# PX4FMUv2_4_6_10.net
KiCad netlist of a schematic drawn in Altium Designer
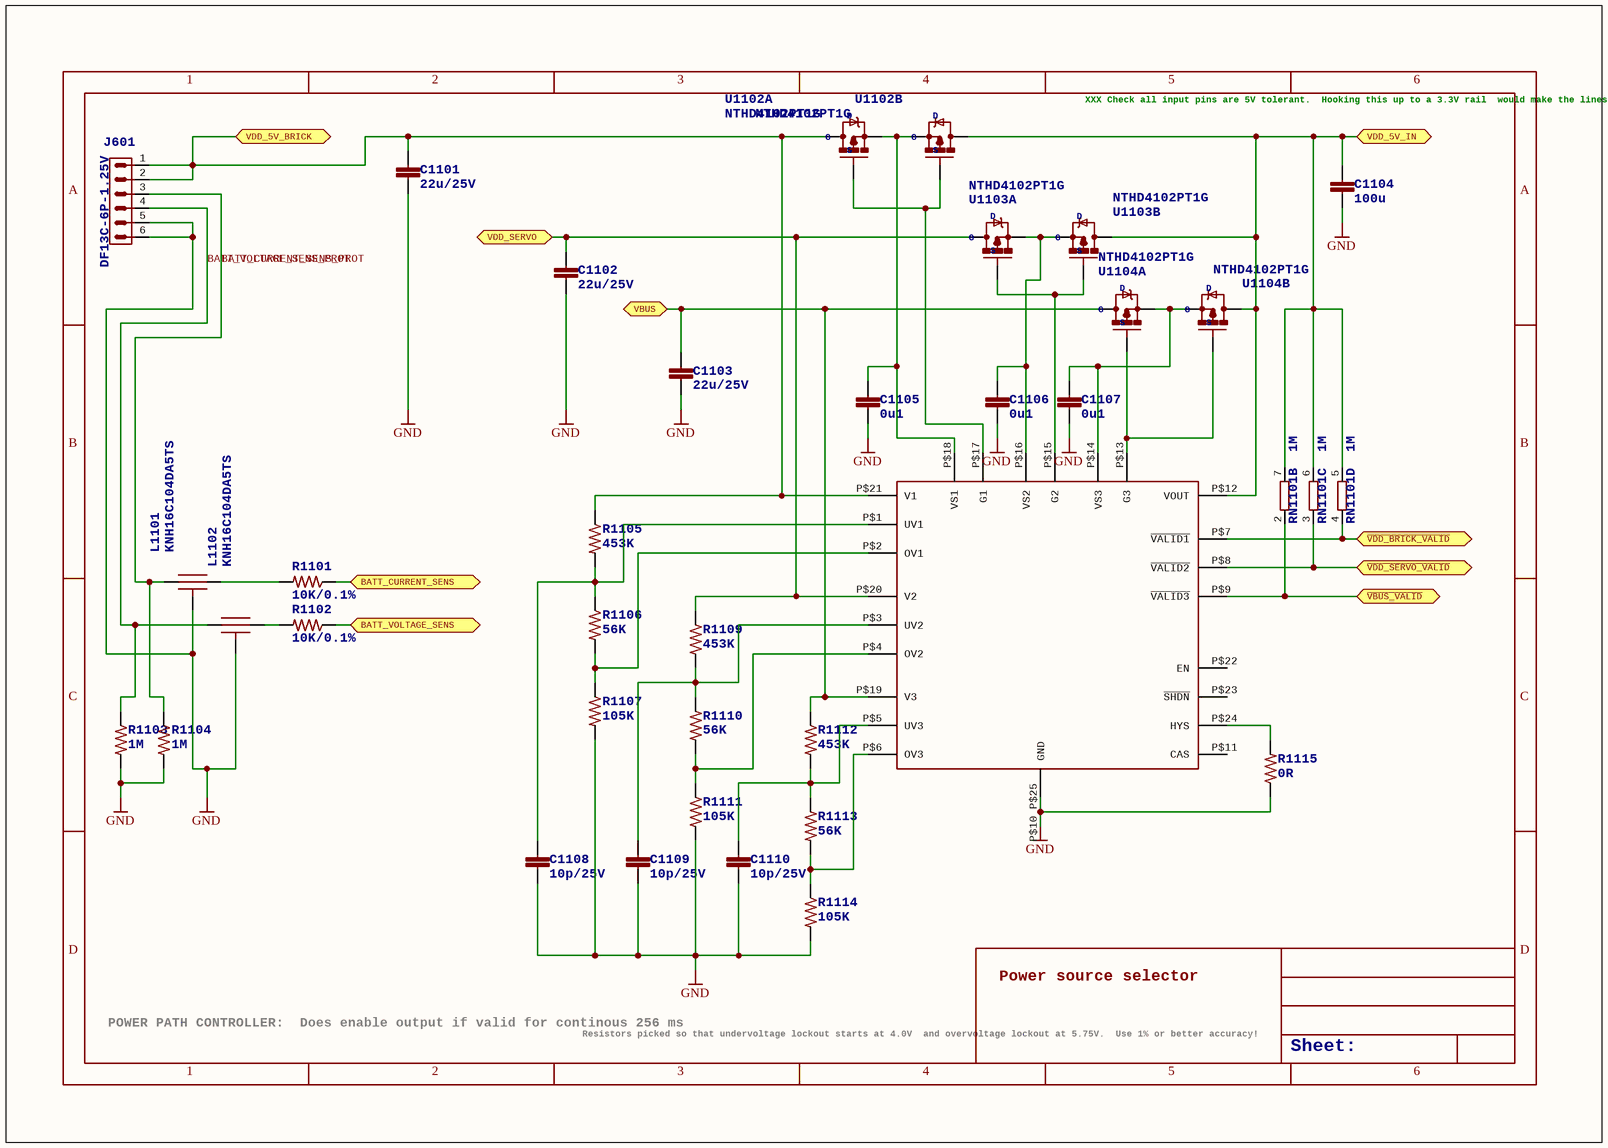
[diagram p0: PX4FMUv2.4.6_10.SchDoc]

(export (version "E")
  (design (tool "Eeschema 10.0.6"))
  (components
    (comp (ref "C1101")
      (value "22u/25V")
      (footprint "0805-CAP")
      (description "CapacitorStandard 0603 ceramic capacitor, and 0.1\" leaded capacitor.")
      (fields (field (name "PARTNO") "CL21A226MAQNNNE"))
      (libsource (lib "pixhawk2") (part "CAP0805"))
    )
    (comp (ref "C1102")
      (value "22u/25V")
      (footprint "0805-CAP")
      (description "CapacitorStandard 0603 ceramic capacitor, and 0.1\" leaded capacitor.")
      (fields (field (name "PARTNO") "CL21A226MAQNNNE"))
      (libsource (lib "pixhawk2") (part "CAP0805"))
    )
    (comp (ref "C1103")
      (value "22u/25V")
      (footprint "0805-CAP")
      (description "CapacitorStandard 0603 ceramic capacitor, and 0.1\" leaded capacitor.")
      (fields (field (name "PARTNO") "CL21A226MAQNNNE"))
      (libsource (lib "pixhawk2") (part "CAP0805"))
    )
    (comp (ref "C1104")
      (value "100u")
      (footprint "1206-CAP")
      (description "CapacitorStandard 0603 ceramic capacitor, and 0.1\" leaded capacitor.")
      (fields (field (name "PARTNO") "C3216X5R1A107M160AC"))
      (libsource (lib "pixhawk2") (part "CAP1206"))
    )
    (comp (ref "C1105")
      (value "0u1")
      (footprint "0402-CAP")
      (description "CapacitorStandard 0603 ceramic capacitor, and 0.1\" leaded capacitor.")
      (fields (field (name "PARTNO") "C1005X7R1E104K050BB"))
      (libsource (lib "pixhawk2") (part "CAP0402"))
    )
    (comp (ref "C1106")
      (value "0u1")
      (footprint "0402-CAP")
      (description "CapacitorStandard 0603 ceramic capacitor, and 0.1\" leaded capacitor.")
      (fields (field (name "PARTNO") "C1005X7R1E104K050BB"))
      (libsource (lib "pixhawk2") (part "CAP0402"))
    )
    (comp (ref "C1107")
      (value "0u1")
      (footprint "0402-CAP")
      (description "CapacitorStandard 0603 ceramic capacitor, and 0.1\" leaded capacitor.")
      (fields (field (name "PARTNO") "C1005X7R1E104K050BB"))
      (libsource (lib "pixhawk2") (part "CAP0402"))
    )
    (comp (ref "C1108")
      (value "10p/25V")
      (footprint "0402-CAP")
      (description "CapacitorStandard 0603 ceramic capacitor, and 0.1\" leaded capacitor.")
      (fields (field (name "PARTNO") "C0402C100J3GACTU"))
      (libsource (lib "pixhawk2") (part "CAP0402"))
    )
    (comp (ref "C1109")
      (value "10p/25V")
      (footprint "0402-CAP")
      (description "CapacitorStandard 0603 ceramic capacitor, and 0.1\" leaded capacitor.")
      (fields (field (name "PARTNO") "C0402C100J3GACTU"))
      (libsource (lib "pixhawk2") (part "CAP0402"))
    )
    (comp (ref "C1110")
      (value "10p/25V")
      (footprint "0402-CAP")
      (description "CapacitorStandard 0603 ceramic capacitor, and 0.1\" leaded capacitor.")
      (fields (field (name "PARTNO") "C0402C100J3GACTU"))
      (libsource (lib "pixhawk2") (part "CAP0402"))
    )
    (comp (ref "J601")
      (value "DF13C-6P-1.25V")
      (footprint "DF13C-6P-1.25V")
      (description "DF13-6P 1.25mm Pitch Miniature Crimping Connector.")
      (libsource (lib "con-hirose-df13") (part "DF13-6P-1.25V"))
    )
    (comp (ref "L1101")
      (value "KNH16C104DA5TS")
      (footprint "KYOCERA-KNH16-DA")
      (description "Kyocera KNH16C104DA5TS EMI filter")
      (libsource (lib "pixhawk2") (part "KNH16C104DA5TS"))
    )
    (comp (ref "L1102")
      (value "KNH16C104DA5TS")
      (footprint "KYOCERA-KNH16-DA")
      (description "Kyocera KNH16C104DA5TS EMI filter")
      (libsource (lib "pixhawk2") (part "KNH16C104DA5TS"))
    )
    (comp (ref "R1101")
      (value "10K/0.1%")
      (footprint "0402-RES")
      (fields (field (name "PARTNO") "ERA-2AEB103X"))
      (libsource (lib "pixhawk2") (part "RESISTOR0402-RES"))
    )
    (comp (ref "R1102")
      (value "10K/0.1%")
      (footprint "0402-RES")
      (fields (field (name "PARTNO") "ERA-2AEB103X"))
      (libsource (lib "pixhawk2") (part "RESISTOR0402-RES"))
    )
    (comp (ref "R1103")
      (value "1M")
      (footprint "0402-RES")
      (fields (field (name "PARTNO") "RC0402FR-071ML"))
      (libsource (lib "pixhawk2") (part "RESISTOR0402-RES"))
    )
    (comp (ref "R1104")
      (value "1M")
      (footprint "0402-RES")
      (fields (field (name "PARTNO") "RC0402FR-071ML"))
      (libsource (lib "pixhawk2") (part "RESISTOR0402-RES"))
    )
    (comp (ref "R1105")
      (value "453K")
      (footprint "0402-RES")
      (fields (field (name "PARTNO") "RMCF0402FT453K"))
      (libsource (lib "pixhawk2") (part "RESISTOR0402-RES"))
    )
    (comp (ref "R1106")
      (value "56K")
      (footprint "0402-RES")
      (fields (field (name "PARTNO") "ERA-2AEB563X"))
      (libsource (lib "pixhawk2") (part "RESISTOR0402-RES"))
    )
    (comp (ref "R1107")
      (value "105K")
      (footprint "0402-RES")
      (fields (field (name "PARTNO") "ERJ-2RKF1053X"))
      (libsource (lib "pixhawk2") (part "RESISTOR0402-RES"))
    )
    (comp (ref "R1109")
      (value "453K")
      (footprint "0402-RES")
      (fields (field (name "PARTNO") "RMCF0402FT453K"))
      (libsource (lib "pixhawk2") (part "RESISTOR0402-RES"))
    )
    (comp (ref "R1110")
      (value "56K")
      (footprint "0402-RES")
      (fields (field (name "PARTNO") "ERA-2AEB563X"))
      (libsource (lib "pixhawk2") (part "RESISTOR0402-RES"))
    )
    (comp (ref "R1111")
      (value "105K")
      (footprint "0402-RES")
      (fields (field (name "PARTNO") "ERJ-2RKF1053X"))
      (libsource (lib "pixhawk2") (part "RESISTOR0402-RES"))
    )
    (comp (ref "R1112")
      (value "453K")
      (footprint "0402-RES")
      (fields (field (name "PARTNO") "RMCF0402FT453K"))
      (libsource (lib "pixhawk2") (part "RESISTOR0402-RES"))
    )
    (comp (ref "R1113")
      (value "56K")
      (footprint "0402-RES")
      (fields (field (name "PARTNO") "ERA-2AEB563X"))
      (libsource (lib "pixhawk2") (part "RESISTOR0402-RES"))
    )
    (comp (ref "R1114")
      (value "105K")
      (footprint "0402-RES")
      (fields (field (name "PARTNO") "ERJ-2RKF1053X"))
      (libsource (lib "pixhawk2") (part "RESISTOR0402-RES"))
    )
    (comp (ref "R1115")
      (value "0R")
      (footprint "0402-RES")
      (fields (field (name "PARTNO") "ERJ-2GE0R00X"))
      (libsource (lib "pixhawk2") (part "RESISTOR0402-RES"))
    )
    (comp (ref "RN1101")
      (value "1M")
      (footprint "EXB28V")
      (description "Array Chip Resistor   Source: RS Component / Phycomp")
      (fields (field (name "PARTNO") "EXB-28V105JX"))
      (libsource (lib "resistor-dil") (part "4R-NEXB28V"))
    )
    (comp (ref "U1101")
      (value "LTC4417")
      (footprint "MO-220")
      (fields (field (name "PARTNO") "LTC4417IUF#PBF"))
      (libsource (lib "pixhawk2") (part "LTC4117"))
    )
    (comp (ref "U1102")
      (value "NTHD4102PT1G")
      (footprint "1206-8")
      (fields (field (name "D") "D") (field (name "S") "S") (field (name "G") "G"))
      (libsource (lib "pixhawk2") (part "MOSFET-DUAL-PCHANNEL-CHIPFET"))
    )
    (comp (ref "U1103")
      (value "NTHD4102PT1G")
      (footprint "1206-8")
      (fields (field (name "D") "D") (field (name "S") "S") (field (name "G") "G"))
      (libsource (lib "pixhawk2") (part "MOSFET-DUAL-PCHANNEL-CHIPFET"))
    )
    (comp (ref "U1104")
      (value "NTHD4102PT1G")
      (footprint "1206-8")
      (fields (field (name "D") "D") (field (name "S") "S") (field (name "G") "G"))
      (libsource (lib "") (part "MOSFET-DUAL-PCHANNEL-CHIPFET_1"))
    )
  )
  (nets
    (net (code "1") (name "/BATT_CURRENT_SENS") (class "Default")
      (node (ref "R1101") (pin "P$1") (pinfunction "1_P$1") (pintype "passive"))
    )
    (net (code "2") (name "/BATT_CURRENT_SENS_PROT") (class "Default")
      (node (ref "J601") (pin "3") (pinfunction "3_3") (pintype "passive"))
      (node (ref "L1101") (pin "P$1") (pinfunction "P$1_P$1") (pintype "passive"))
      (node (ref "R1104") (pin "P$1") (pinfunction "1_P$1") (pintype "passive"))
    )
    (net (code "3") (name "/BATT_VOLTAGE_SENS") (class "Default")
      (node (ref "R1102") (pin "P$1") (pinfunction "1_P$1") (pintype "passive"))
    )
    (net (code "4") (name "/BATT_VOLTAGE_SENS_PROT") (class "Default")
      (node (ref "J601") (pin "4") (pinfunction "4_4") (pintype "passive"))
      (node (ref "L1102") (pin "P$1") (pinfunction "P$1_P$1") (pintype "passive"))
      (node (ref "R1103") (pin "P$1") (pinfunction "1_P$1") (pintype "passive"))
    )
    (net (code "5") (name "/VBUS") (class "Default")
      (node (ref "C1103") (pin "P$1") (pinfunction "1_P$1") (pintype "passive"))
      (node (ref "R1112") (pin "P$1") (pinfunction "1_P$1") (pintype "passive"))
      (node (ref "U1101") (pin "P$19") (pinfunction "V3_P$19") (pintype "passive"))
      (node (ref "U1104") (pin "P$7_P$8") (pinfunction "D_P$7_P$8") (pintype "passive"))
    )
    (net (code "6") (name "/VDD_5V_BRICK") (class "Default")
      (node (ref "C1101") (pin "P$1") (pinfunction "1_P$1") (pintype "passive"))
      (node (ref "J601") (pin "1") (pinfunction "1_1") (pintype "passive"))
      (node (ref "J601") (pin "2") (pinfunction "2_2") (pintype "passive"))
      (node (ref "R1105") (pin "P$1") (pinfunction "1_P$1") (pintype "passive"))
      (node (ref "U1101") (pin "P$21") (pinfunction "V1_P$21") (pintype "passive"))
      (node (ref "U1102") (pin "P$7_P$8") (pinfunction "D_P$7_P$8") (pintype "passive"))
    )
    (net (code "7") (name "/VDD_5V_IN") (class "Default")
      (node (ref "C1104") (pin "P$1") (pinfunction "1_P$1") (pintype "passive"))
      (node (ref "RN1101") (pin "5") (pinfunction "2_5") (pintype "passive"))
      (node (ref "RN1101") (pin "6") (pinfunction "2_6") (pintype "passive"))
      (node (ref "RN1101") (pin "7") (pinfunction "2_7") (pintype "passive"))
      (node (ref "U1101") (pin "P$12") (pinfunction "VOUT_P$12") (pintype "passive"))
      (node (ref "U1102") (pin "P$5_P$6") (pinfunction "D_P$5_P$6") (pintype "passive"))
      (node (ref "U1103") (pin "P$5_P$6") (pinfunction "D_P$5_P$6") (pintype "passive"))
      (node (ref "U1104") (pin "P$5_P$6") (pinfunction "D_P$5_P$6") (pintype "passive"))
    )
    (net (code "8") (name "/VDD_SERVO") (class "Default")
      (node (ref "C1102") (pin "P$1") (pinfunction "1_P$1") (pintype "passive"))
      (node (ref "R1109") (pin "P$1") (pinfunction "1_P$1") (pintype "passive"))
      (node (ref "U1101") (pin "P$20") (pinfunction "V2_P$20") (pintype "passive"))
      (node (ref "U1103") (pin "P$7_P$8") (pinfunction "D_P$7_P$8") (pintype "passive"))
    )
    (net (code "9") (name "/~{VBUS_VALID}") (class "Default")
      (node (ref "RN1101") (pin "2") (pinfunction "1_2") (pintype "passive"))
      (node (ref "U1101") (pin "P$9") (pinfunction "~{VALID3}_P$9") (pintype "passive"))
    )
    (net (code "10") (name "/~{VDD_BRICK_VALID}") (class "Default")
      (node (ref "RN1101") (pin "4") (pinfunction "1_4") (pintype "passive"))
      (node (ref "U1101") (pin "P$7") (pinfunction "~{VALID1}_P$7") (pintype "passive"))
    )
    (net (code "11") (name "/~{VDD_SERVO_VALID}") (class "Default")
      (node (ref "RN1101") (pin "3") (pinfunction "1_3") (pintype "passive"))
      (node (ref "U1101") (pin "P$8") (pinfunction "~{VALID2}_P$8") (pintype "passive"))
    )
    (net (code "12") (name "GND") (class "Default")
      (node (ref "C1101") (pin "P$2") (pinfunction "2_P$2") (pintype "passive"))
      (node (ref "C1102") (pin "P$2") (pinfunction "2_P$2") (pintype "passive"))
      (node (ref "C1103") (pin "P$2") (pinfunction "2_P$2") (pintype "passive"))
      (node (ref "C1104") (pin "P$2") (pinfunction "2_P$2") (pintype "passive"))
      (node (ref "C1105") (pin "P$2") (pinfunction "2_P$2") (pintype "passive"))
      (node (ref "C1106") (pin "P$2") (pinfunction "2_P$2") (pintype "passive"))
      (node (ref "C1107") (pin "P$2") (pinfunction "2_P$2") (pintype "passive"))
      (node (ref "C1108") (pin "P$2") (pinfunction "2_P$2") (pintype "passive"))
      (node (ref "C1109") (pin "P$2") (pinfunction "2_P$2") (pintype "passive"))
      (node (ref "C1110") (pin "P$2") (pinfunction "2_P$2") (pintype "passive"))
      (node (ref "J601") (pin "5") (pinfunction "5_5") (pintype "passive"))
      (node (ref "J601") (pin "6") (pinfunction "6_6") (pintype "passive"))
      (node (ref "L1101") (pin "P$3_P$4_P$5") (pinfunction "P$3_P$3_P$4_P$5") (pintype "passive"))
      (node (ref "L1102") (pin "P$3_P$4_P$5") (pinfunction "P$3_P$3_P$4_P$5") (pintype "passive"))
      (node (ref "R1103") (pin "P$2") (pinfunction "2_P$2") (pintype "passive"))
      (node (ref "R1104") (pin "P$2") (pinfunction "2_P$2") (pintype "passive"))
      (node (ref "R1107") (pin "P$2") (pinfunction "2_P$2") (pintype "passive"))
      (node (ref "R1111") (pin "P$2") (pinfunction "2_P$2") (pintype "passive"))
      (node (ref "R1114") (pin "P$2") (pinfunction "2_P$2") (pintype "passive"))
      (node (ref "R1115") (pin "P$1") (pinfunction "1_P$1") (pintype "passive"))
      (node (ref "U1101") (pin "P$10_P$25") (pinfunction "GND_P$10_P$25") (pintype "passive"))
    )
    (net (code "13") (name "Net-(C1105-1)") (class "Default")
      (node (ref "C1105") (pin "P$1") (pinfunction "1_P$1") (pintype "passive"))
      (node (ref "U1101") (pin "P$18") (pinfunction "VS1_P$18") (pintype "passive"))
      (node (ref "U1102") (pin "P$1") (pinfunction "S_P$1") (pintype "passive"))
      (node (ref "U1102") (pin "P$3") (pinfunction "S_P$3") (pintype "passive"))
    )
    (net (code "14") (name "Net-(C1106-1)") (class "Default")
      (node (ref "C1106") (pin "P$1") (pinfunction "1_P$1") (pintype "passive"))
      (node (ref "U1101") (pin "P$16") (pinfunction "VS2_P$16") (pintype "passive"))
      (node (ref "U1103") (pin "P$1") (pinfunction "S_P$1") (pintype "passive"))
      (node (ref "U1103") (pin "P$3") (pinfunction "S_P$3") (pintype "passive"))
    )
    (net (code "15") (name "Net-(C1107-1)") (class "Default")
      (node (ref "C1107") (pin "P$1") (pinfunction "1_P$1") (pintype "passive"))
      (node (ref "U1101") (pin "P$14") (pinfunction "VS3_P$14") (pintype "passive"))
      (node (ref "U1104") (pin "P$1") (pinfunction "S_P$1") (pintype "passive"))
      (node (ref "U1104") (pin "P$3") (pinfunction "S_P$3") (pintype "passive"))
    )
    (net (code "16") (name "Net-(C1108-1)") (class "Default")
      (node (ref "C1108") (pin "P$1") (pinfunction "1_P$1") (pintype "passive"))
      (node (ref "R1105") (pin "P$2") (pinfunction "2_P$2") (pintype "passive"))
      (node (ref "R1106") (pin "P$1") (pinfunction "1_P$1") (pintype "passive"))
      (node (ref "U1101") (pin "P$1") (pinfunction "UV1_P$1") (pintype "passive"))
    )
    (net (code "17") (name "Net-(C1109-1)") (class "Default")
      (node (ref "C1109") (pin "P$1") (pinfunction "1_P$1") (pintype "passive"))
      (node (ref "R1109") (pin "P$2") (pinfunction "2_P$2") (pintype "passive"))
      (node (ref "R1110") (pin "P$1") (pinfunction "1_P$1") (pintype "passive"))
      (node (ref "U1101") (pin "P$3") (pinfunction "UV2_P$3") (pintype "passive"))
    )
    (net (code "18") (name "Net-(C1110-1)") (class "Default")
      (node (ref "C1110") (pin "P$1") (pinfunction "1_P$1") (pintype "passive"))
      (node (ref "R1112") (pin "P$2") (pinfunction "2_P$2") (pintype "passive"))
      (node (ref "R1113") (pin "P$1") (pinfunction "1_P$1") (pintype "passive"))
      (node (ref "U1101") (pin "P$5") (pinfunction "UV3_P$5") (pintype "passive"))
    )
    (net (code "19") (name "Net-(R1101-2)") (class "Default")
      (node (ref "L1101") (pin "P$2") (pinfunction "P$2_P$2") (pintype "passive"))
      (node (ref "R1101") (pin "P$2") (pinfunction "2_P$2") (pintype "passive"))
    )
    (net (code "20") (name "Net-(R1102-2)") (class "Default")
      (node (ref "L1102") (pin "P$2") (pinfunction "P$2_P$2") (pintype "passive"))
      (node (ref "R1102") (pin "P$2") (pinfunction "2_P$2") (pintype "passive"))
    )
    (net (code "21") (name "Net-(R1106-2)") (class "Default")
      (node (ref "R1106") (pin "P$2") (pinfunction "2_P$2") (pintype "passive"))
      (node (ref "R1107") (pin "P$1") (pinfunction "1_P$1") (pintype "passive"))
      (node (ref "U1101") (pin "P$2") (pinfunction "OV1_P$2") (pintype "passive"))
    )
    (net (code "22") (name "Net-(R1110-2)") (class "Default")
      (node (ref "R1110") (pin "P$2") (pinfunction "2_P$2") (pintype "passive"))
      (node (ref "R1111") (pin "P$1") (pinfunction "1_P$1") (pintype "passive"))
      (node (ref "U1101") (pin "P$4") (pinfunction "OV2_P$4") (pintype "passive"))
    )
    (net (code "23") (name "Net-(R1113-2)") (class "Default")
      (node (ref "R1113") (pin "P$2") (pinfunction "2_P$2") (pintype "passive"))
      (node (ref "R1114") (pin "P$1") (pinfunction "1_P$1") (pintype "passive"))
      (node (ref "U1101") (pin "P$6") (pinfunction "OV3_P$6") (pintype "passive"))
    )
    (net (code "24") (name "Net-(R1115-2)") (class "Default")
      (node (ref "R1115") (pin "P$2") (pinfunction "2_P$2") (pintype "passive"))
      (node (ref "U1101") (pin "P$24") (pinfunction "HYS_P$24") (pintype "passive"))
    )
    (net (code "25") (name "Net-(U1101-G1)") (class "Default")
      (node (ref "U1101") (pin "P$17") (pinfunction "G1_P$17") (pintype "passive"))
      (node (ref "U1102") (pin "P$2") (pinfunction "G_P$2") (pintype "passive"))
      (node (ref "U1102") (pin "P$4") (pinfunction "G_P$4") (pintype "passive"))
    )
    (net (code "26") (name "Net-(U1101-G2)") (class "Default")
      (node (ref "U1101") (pin "P$15") (pinfunction "G2_P$15") (pintype "passive"))
      (node (ref "U1103") (pin "P$2") (pinfunction "G_P$2") (pintype "passive"))
      (node (ref "U1103") (pin "P$4") (pinfunction "G_P$4") (pintype "passive"))
    )
    (net (code "27") (name "Net-(U1101-G3)") (class "Default")
      (node (ref "U1101") (pin "P$13") (pinfunction "G3_P$13") (pintype "passive"))
      (node (ref "U1104") (pin "P$2") (pinfunction "G_P$2") (pintype "passive"))
      (node (ref "U1104") (pin "P$4") (pinfunction "G_P$4") (pintype "passive"))
    )
    (net (code "28") (name "unconnected-(U1101-CAS-PadP$11)") (class "Default")
      (node (ref "U1101") (pin "P$11") (pinfunction "CAS_P$11") (pintype "passive"))
    )
    (net (code "29") (name "unconnected-(U1101-EN-PadP$22)") (class "Default")
      (node (ref "U1101") (pin "P$22") (pinfunction "EN_P$22") (pintype "passive"))
    )
    (net (code "30") (name "unconnected-(U1101-~{SHDN}-PadP$23)") (class "Default")
      (node (ref "U1101") (pin "P$23") (pinfunction "~{SHDN}_P$23") (pintype "passive"))
    )
  )
)
